# 7seg2.net
KiCad netlist of a schematic drawn in EAGLE
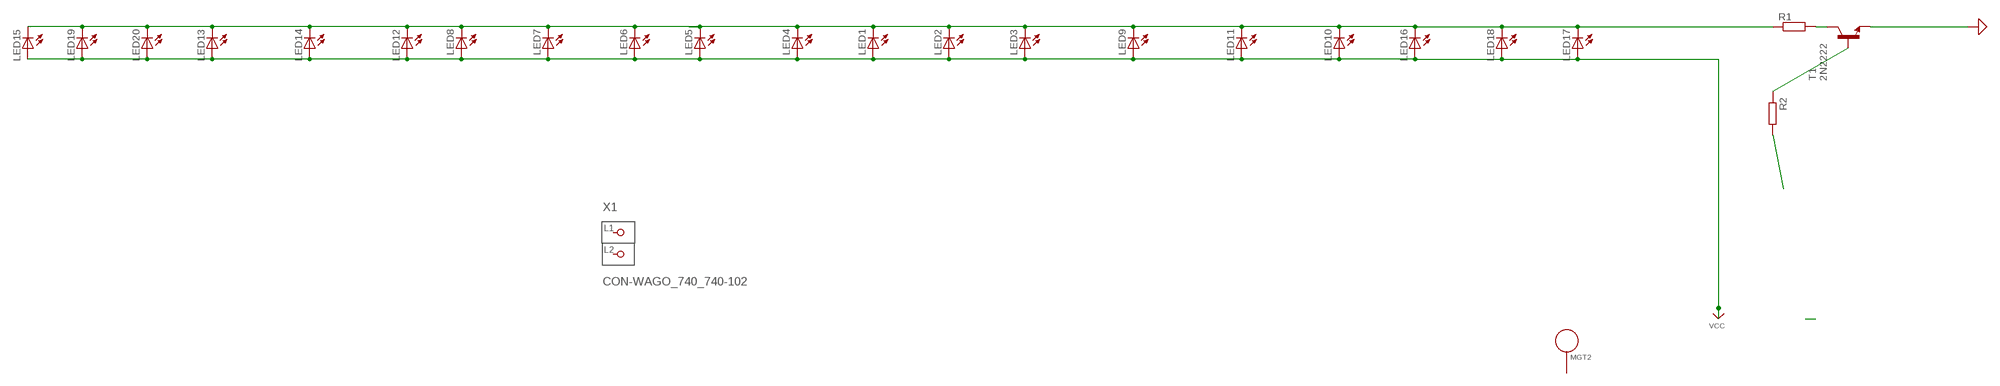
[diagram p0: schematic, sheet 1]
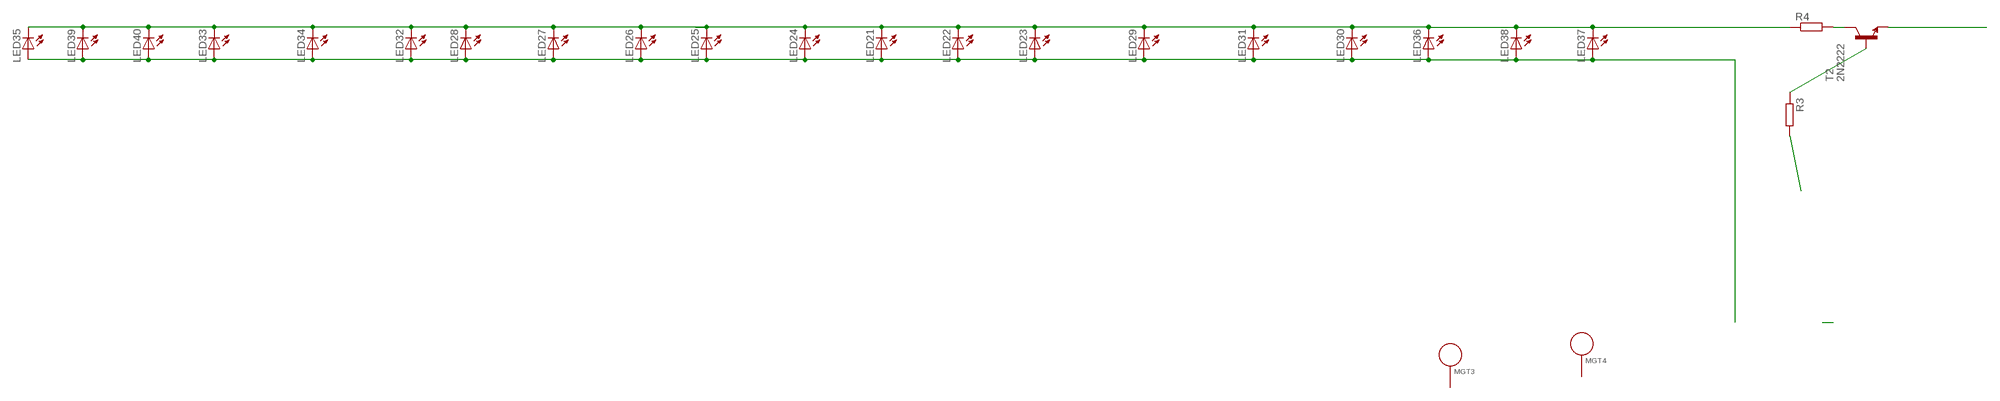
[diagram p1: schematic, sheet 2]
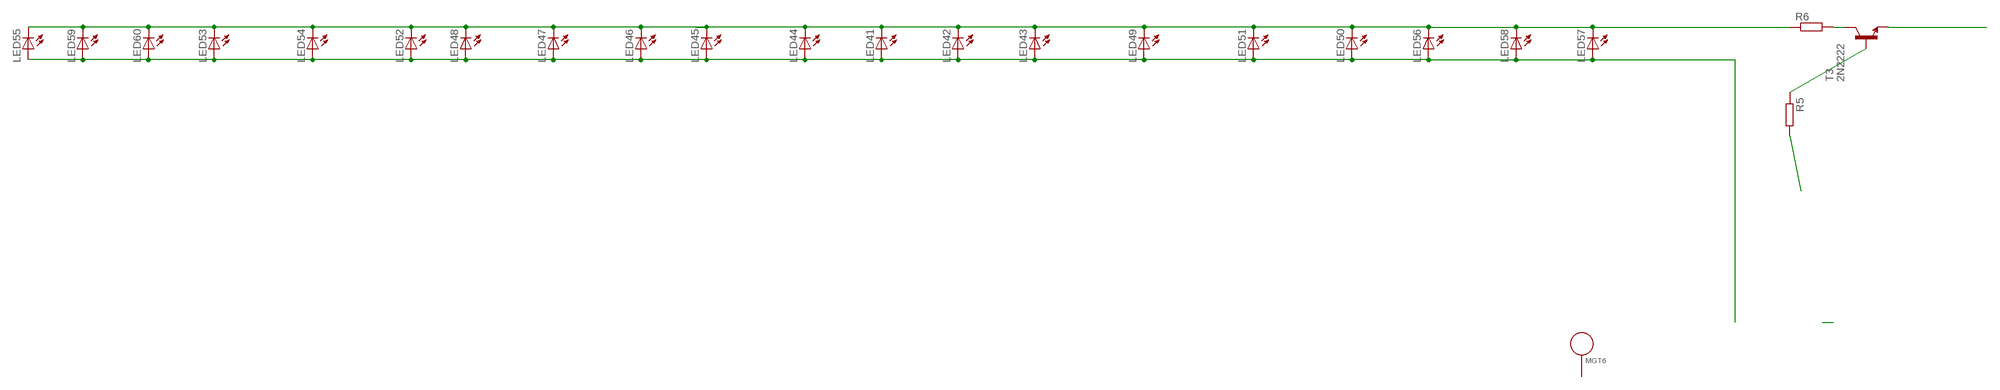
[diagram p2: schematic, sheet 3]
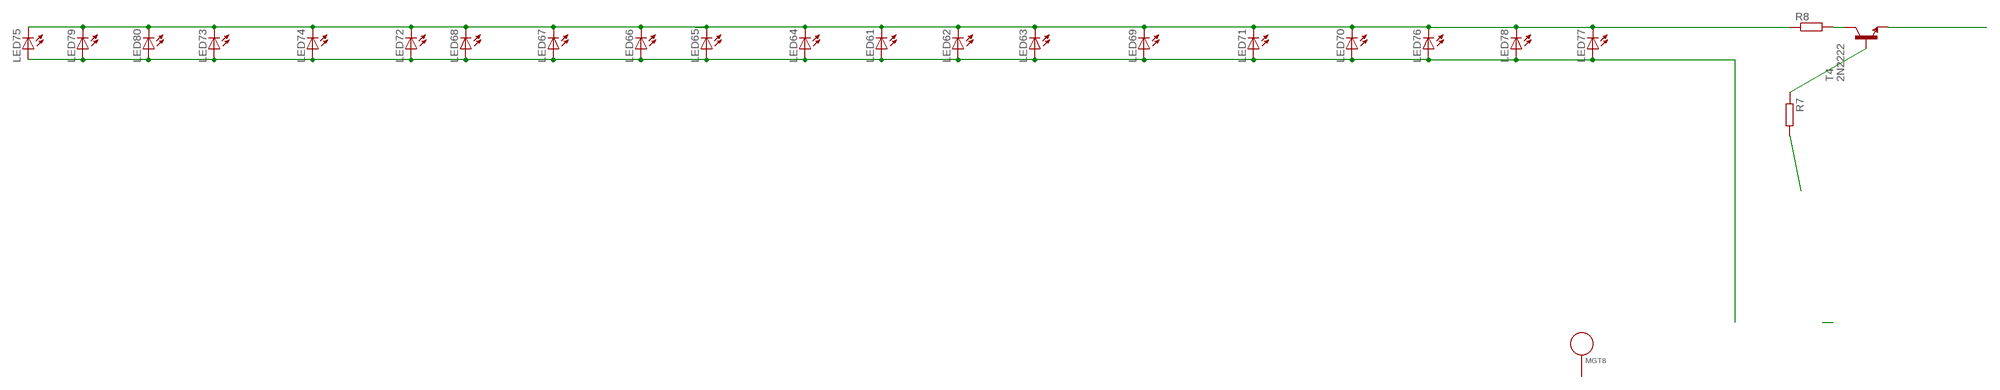
[diagram p3: schematic, sheet 4]
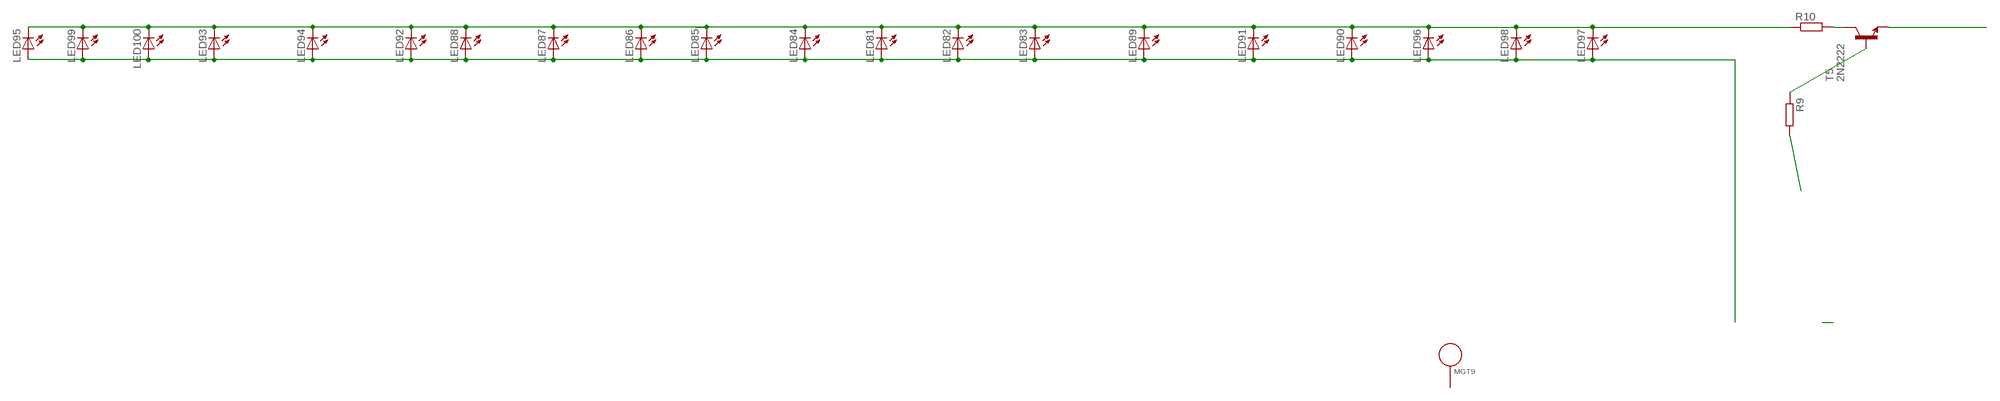
[diagram p4: schematic, sheet 5]
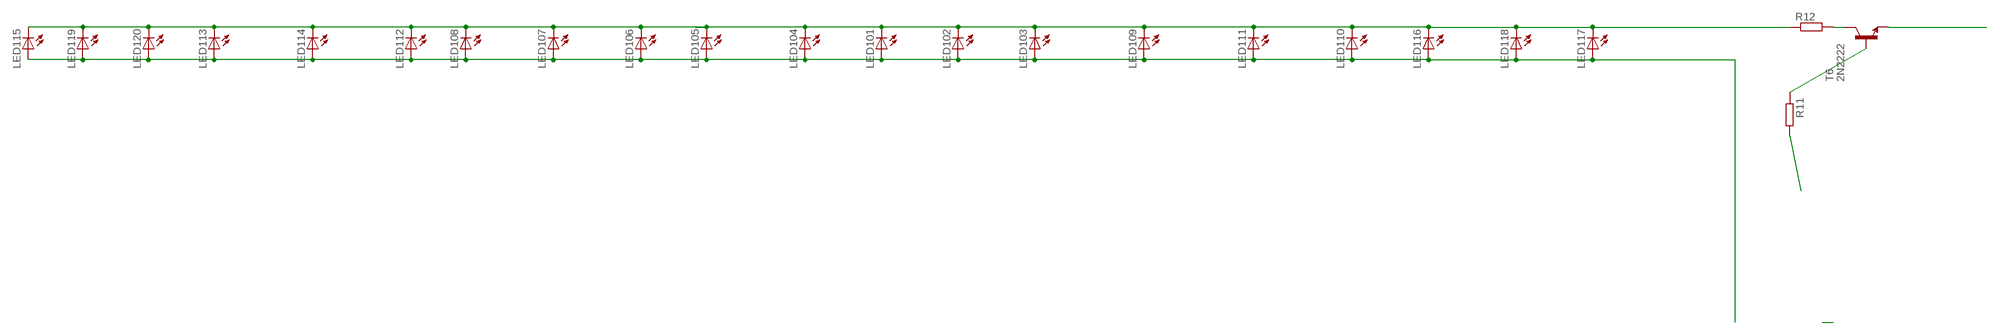
[diagram p5: schematic, sheet 6]
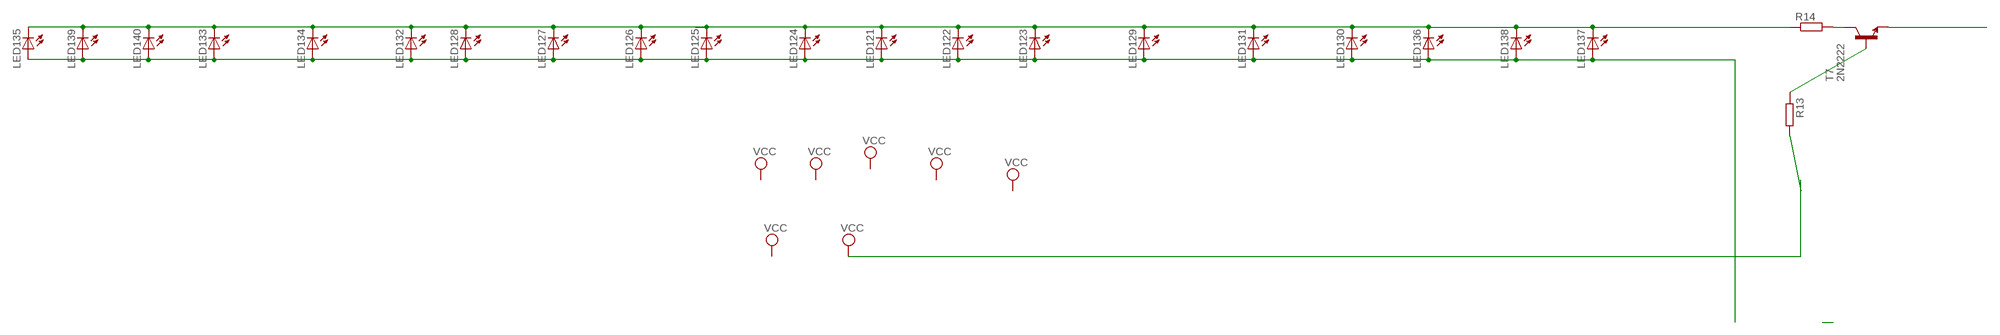
[diagram p6: schematic, sheet 7]

(export (version "E")
  (design (tool "Eeschema 10.0.6"))
  (components
    (comp (ref "LED41")
      (value "LED5MM")
      (footprint "eagle-import:LED5MM")
      (libsource (lib "eagle-import") (part "LED5MM"))
    )
    (comp (ref "LED42")
      (value "LED5MM")
      (footprint "eagle-import:LED5MM")
      (libsource (lib "eagle-import") (part "LED5MM"))
    )
    (comp (ref "LED43")
      (value "LED5MM")
      (footprint "eagle-import:LED5MM")
      (libsource (lib "eagle-import") (part "LED5MM"))
    )
    (comp (ref "LED44")
      (value "LED5MM")
      (footprint "eagle-import:LED5MM")
      (libsource (lib "eagle-import") (part "LED5MM"))
    )
    (comp (ref "LED45")
      (value "LED5MM")
      (footprint "eagle-import:LED5MM")
      (libsource (lib "eagle-import") (part "LED5MM"))
    )
    (comp (ref "LED46")
      (value "LED5MM")
      (footprint "eagle-import:LED5MM")
      (libsource (lib "eagle-import") (part "LED5MM"))
    )
    (comp (ref "LED47")
      (value "LED5MM")
      (footprint "eagle-import:LED5MM")
      (libsource (lib "eagle-import") (part "LED5MM"))
    )
    (comp (ref "LED48")
      (value "LED5MM")
      (footprint "eagle-import:LED5MM")
      (libsource (lib "eagle-import") (part "LED5MM"))
    )
    (comp (ref "LED49")
      (value "LED5MM")
      (footprint "eagle-import:LED5MM")
      (libsource (lib "eagle-import") (part "LED5MM"))
    )
    (comp (ref "LED50")
      (value "LED5MM")
      (footprint "eagle-import:LED5MM")
      (libsource (lib "eagle-import") (part "LED5MM"))
    )
    (comp (ref "LED51")
      (value "LED5MM")
      (footprint "eagle-import:LED5MM")
      (libsource (lib "eagle-import") (part "LED5MM"))
    )
    (comp (ref "LED52")
      (value "LED5MM")
      (footprint "eagle-import:LED5MM")
      (libsource (lib "eagle-import") (part "LED5MM"))
    )
    (comp (ref "LED53")
      (value "LED5MM")
      (footprint "eagle-import:LED5MM")
      (libsource (lib "eagle-import") (part "LED5MM"))
    )
    (comp (ref "LED54")
      (value "LED5MM")
      (footprint "eagle-import:LED5MM")
      (libsource (lib "eagle-import") (part "LED5MM"))
    )
    (comp (ref "LED55")
      (value "LED5MM")
      (footprint "eagle-import:LED5MM")
      (libsource (lib "eagle-import") (part "LED5MM"))
    )
    (comp (ref "LED56")
      (value "LED5MM")
      (footprint "eagle-import:LED5MM")
      (libsource (lib "eagle-import") (part "LED5MM"))
    )
    (comp (ref "LED57")
      (value "LED5MM")
      (footprint "eagle-import:LED5MM")
      (libsource (lib "eagle-import") (part "LED5MM"))
    )
    (comp (ref "LED58")
      (value "LED5MM")
      (footprint "eagle-import:LED5MM")
      (libsource (lib "eagle-import") (part "LED5MM"))
    )
    (comp (ref "LED59")
      (value "LED5MM")
      (footprint "eagle-import:LED5MM")
      (libsource (lib "eagle-import") (part "LED5MM"))
    )
    (comp (ref "LED60")
      (value "LED5MM")
      (footprint "eagle-import:LED5MM")
      (libsource (lib "eagle-import") (part "LED5MM"))
    )
    (comp (ref "MGT6")
      (value "BEAGLEBONEBLACK_MOUNTING_HOLE")
      (footprint "eagle-import:BEAGLEBONEBLACK_MOUNTING_HOLE")
      (libsource (lib "eagle-import") (part "BEAGLEBONEBLACK_MOUNTING_HOLE"))
    )
    (comp (ref "R5")
      (value "R-EU_0207/10")
      (footprint "eagle-import:0207_10")
      (libsource (lib "eagle-import") (part "R-EU_0207/10"))
    )
    (comp (ref "R6")
      (value "R-EU_0207/10")
      (footprint "eagle-import:0207_10")
      (libsource (lib "eagle-import") (part "R-EU_0207/10"))
    )
    (comp (ref "T3")
      (value "2N2222")
      (footprint "eagle-import:TO92-EBC-OVAL")
      (libsource (lib "eagle-import") (part "2N2222"))
    )
    (comp (ref "LED101")
      (value "LED5MM")
      (footprint "eagle-import:LED5MM")
      (libsource (lib "eagle-import") (part "LED5MM"))
    )
    (comp (ref "LED102")
      (value "LED5MM")
      (footprint "eagle-import:LED5MM")
      (libsource (lib "eagle-import") (part "LED5MM"))
    )
    (comp (ref "LED103")
      (value "LED5MM")
      (footprint "eagle-import:LED5MM")
      (libsource (lib "eagle-import") (part "LED5MM"))
    )
    (comp (ref "LED104")
      (value "LED5MM")
      (footprint "eagle-import:LED5MM")
      (libsource (lib "eagle-import") (part "LED5MM"))
    )
    (comp (ref "LED105")
      (value "LED5MM")
      (footprint "eagle-import:LED5MM")
      (libsource (lib "eagle-import") (part "LED5MM"))
    )
    (comp (ref "LED106")
      (value "LED5MM")
      (footprint "eagle-import:LED5MM")
      (libsource (lib "eagle-import") (part "LED5MM"))
    )
    (comp (ref "LED107")
      (value "LED5MM")
      (footprint "eagle-import:LED5MM")
      (libsource (lib "eagle-import") (part "LED5MM"))
    )
    (comp (ref "LED108")
      (value "LED5MM")
      (footprint "eagle-import:LED5MM")
      (libsource (lib "eagle-import") (part "LED5MM"))
    )
    (comp (ref "LED109")
      (value "LED5MM")
      (footprint "eagle-import:LED5MM")
      (libsource (lib "eagle-import") (part "LED5MM"))
    )
    (comp (ref "LED110")
      (value "LED5MM")
      (footprint "eagle-import:LED5MM")
      (libsource (lib "eagle-import") (part "LED5MM"))
    )
    (comp (ref "LED111")
      (value "LED5MM")
      (footprint "eagle-import:LED5MM")
      (libsource (lib "eagle-import") (part "LED5MM"))
    )
    (comp (ref "LED112")
      (value "LED5MM")
      (footprint "eagle-import:LED5MM")
      (libsource (lib "eagle-import") (part "LED5MM"))
    )
    (comp (ref "LED113")
      (value "LED5MM")
      (footprint "eagle-import:LED5MM")
      (libsource (lib "eagle-import") (part "LED5MM"))
    )
    (comp (ref "LED114")
      (value "LED5MM")
      (footprint "eagle-import:LED5MM")
      (libsource (lib "eagle-import") (part "LED5MM"))
    )
    (comp (ref "LED115")
      (value "LED5MM")
      (footprint "eagle-import:LED5MM")
      (libsource (lib "eagle-import") (part "LED5MM"))
    )
    (comp (ref "LED116")
      (value "LED5MM")
      (footprint "eagle-import:LED5MM")
      (libsource (lib "eagle-import") (part "LED5MM"))
    )
    (comp (ref "LED117")
      (value "LED5MM")
      (footprint "eagle-import:LED5MM")
      (libsource (lib "eagle-import") (part "LED5MM"))
    )
    (comp (ref "LED118")
      (value "LED5MM")
      (footprint "eagle-import:LED5MM")
      (libsource (lib "eagle-import") (part "LED5MM"))
    )
    (comp (ref "LED119")
      (value "LED5MM")
      (footprint "eagle-import:LED5MM")
      (libsource (lib "eagle-import") (part "LED5MM"))
    )
    (comp (ref "LED120")
      (value "LED5MM")
      (footprint "eagle-import:LED5MM")
      (libsource (lib "eagle-import") (part "LED5MM"))
    )
    (comp (ref "R11")
      (value "R-EU_0207/10")
      (footprint "eagle-import:0207_10")
      (libsource (lib "eagle-import") (part "R-EU_0207/10"))
    )
    (comp (ref "R12")
      (value "R-EU_0207/10")
      (footprint "eagle-import:0207_10")
      (libsource (lib "eagle-import") (part "R-EU_0207/10"))
    )
    (comp (ref "T6")
      (value "2N2222")
      (footprint "eagle-import:TO92-EBC-OVAL")
      (libsource (lib "eagle-import") (part "2N2222"))
    )
    (comp (ref "LED81")
      (value "LED5MM")
      (footprint "eagle-import:LED5MM")
      (libsource (lib "eagle-import") (part "LED5MM"))
    )
    (comp (ref "LED82")
      (value "LED5MM")
      (footprint "eagle-import:LED5MM")
      (libsource (lib "eagle-import") (part "LED5MM"))
    )
    (comp (ref "LED83")
      (value "LED5MM")
      (footprint "eagle-import:LED5MM")
      (libsource (lib "eagle-import") (part "LED5MM"))
    )
    (comp (ref "LED84")
      (value "LED5MM")
      (footprint "eagle-import:LED5MM")
      (libsource (lib "eagle-import") (part "LED5MM"))
    )
    (comp (ref "LED85")
      (value "LED5MM")
      (footprint "eagle-import:LED5MM")
      (libsource (lib "eagle-import") (part "LED5MM"))
    )
    (comp (ref "LED86")
      (value "LED5MM")
      (footprint "eagle-import:LED5MM")
      (libsource (lib "eagle-import") (part "LED5MM"))
    )
    (comp (ref "LED87")
      (value "LED5MM")
      (footprint "eagle-import:LED5MM")
      (libsource (lib "eagle-import") (part "LED5MM"))
    )
    (comp (ref "LED88")
      (value "LED5MM")
      (footprint "eagle-import:LED5MM")
      (libsource (lib "eagle-import") (part "LED5MM"))
    )
    (comp (ref "LED89")
      (value "LED5MM")
      (footprint "eagle-import:LED5MM")
      (libsource (lib "eagle-import") (part "LED5MM"))
    )
    (comp (ref "LED90")
      (value "LED5MM")
      (footprint "eagle-import:LED5MM")
      (libsource (lib "eagle-import") (part "LED5MM"))
    )
    (comp (ref "LED91")
      (value "LED5MM")
      (footprint "eagle-import:LED5MM")
      (libsource (lib "eagle-import") (part "LED5MM"))
    )
    (comp (ref "LED92")
      (value "LED5MM")
      (footprint "eagle-import:LED5MM")
      (libsource (lib "eagle-import") (part "LED5MM"))
    )
    (comp (ref "LED93")
      (value "LED5MM")
      (footprint "eagle-import:LED5MM")
      (libsource (lib "eagle-import") (part "LED5MM"))
    )
    (comp (ref "LED94")
      (value "LED5MM")
      (footprint "eagle-import:LED5MM")
      (libsource (lib "eagle-import") (part "LED5MM"))
    )
    (comp (ref "LED95")
      (value "LED5MM")
      (footprint "eagle-import:LED5MM")
      (libsource (lib "eagle-import") (part "LED5MM"))
    )
    (comp (ref "LED96")
      (value "LED5MM")
      (footprint "eagle-import:LED5MM")
      (libsource (lib "eagle-import") (part "LED5MM"))
    )
    (comp (ref "LED97")
      (value "LED5MM")
      (footprint "eagle-import:LED5MM")
      (libsource (lib "eagle-import") (part "LED5MM"))
    )
    (comp (ref "LED98")
      (value "LED5MM")
      (footprint "eagle-import:LED5MM")
      (libsource (lib "eagle-import") (part "LED5MM"))
    )
    (comp (ref "LED99")
      (value "LED5MM")
      (footprint "eagle-import:LED5MM")
      (libsource (lib "eagle-import") (part "LED5MM"))
    )
    (comp (ref "LED100")
      (value "LED5MM")
      (footprint "eagle-import:LED5MM")
      (libsource (lib "eagle-import") (part "LED5MM"))
    )
    (comp (ref "MGT9")
      (value "BEAGLEBONEBLACK_MOUNTING_HOLE")
      (footprint "eagle-import:BEAGLEBONEBLACK_MOUNTING_HOLE")
      (libsource (lib "eagle-import") (part "BEAGLEBONEBLACK_MOUNTING_HOLE"))
    )
    (comp (ref "R9")
      (value "R-EU_0207/10")
      (footprint "eagle-import:0207_10")
      (libsource (lib "eagle-import") (part "R-EU_0207/10"))
    )
    (comp (ref "R10")
      (value "R-EU_0207/10")
      (footprint "eagle-import:0207_10")
      (libsource (lib "eagle-import") (part "R-EU_0207/10"))
    )
    (comp (ref "T5")
      (value "2N2222")
      (footprint "eagle-import:TO92-EBC-OVAL")
      (libsource (lib "eagle-import") (part "2N2222"))
    )
    (comp (ref "LED21")
      (value "LED5MM")
      (footprint "eagle-import:LED5MM")
      (libsource (lib "eagle-import") (part "LED5MM"))
    )
    (comp (ref "LED22")
      (value "LED5MM")
      (footprint "eagle-import:LED5MM")
      (libsource (lib "eagle-import") (part "LED5MM"))
    )
    (comp (ref "LED23")
      (value "LED5MM")
      (footprint "eagle-import:LED5MM")
      (libsource (lib "eagle-import") (part "LED5MM"))
    )
    (comp (ref "LED24")
      (value "LED5MM")
      (footprint "eagle-import:LED5MM")
      (libsource (lib "eagle-import") (part "LED5MM"))
    )
    (comp (ref "LED25")
      (value "LED5MM")
      (footprint "eagle-import:LED5MM")
      (libsource (lib "eagle-import") (part "LED5MM"))
    )
    (comp (ref "LED26")
      (value "LED5MM")
      (footprint "eagle-import:LED5MM")
      (libsource (lib "eagle-import") (part "LED5MM"))
    )
    (comp (ref "LED27")
      (value "LED5MM")
      (footprint "eagle-import:LED5MM")
      (libsource (lib "eagle-import") (part "LED5MM"))
    )
    (comp (ref "LED28")
      (value "LED5MM")
      (footprint "eagle-import:LED5MM")
      (libsource (lib "eagle-import") (part "LED5MM"))
    )
    (comp (ref "LED29")
      (value "LED5MM")
      (footprint "eagle-import:LED5MM")
      (libsource (lib "eagle-import") (part "LED5MM"))
    )
    (comp (ref "LED30")
      (value "LED5MM")
      (footprint "eagle-import:LED5MM")
      (libsource (lib "eagle-import") (part "LED5MM"))
    )
    (comp (ref "LED31")
      (value "LED5MM")
      (footprint "eagle-import:LED5MM")
      (libsource (lib "eagle-import") (part "LED5MM"))
    )
    (comp (ref "LED32")
      (value "LED5MM")
      (footprint "eagle-import:LED5MM")
      (libsource (lib "eagle-import") (part "LED5MM"))
    )
    (comp (ref "LED33")
      (value "LED5MM")
      (footprint "eagle-import:LED5MM")
      (libsource (lib "eagle-import") (part "LED5MM"))
    )
    (comp (ref "LED34")
      (value "LED5MM")
      (footprint "eagle-import:LED5MM")
      (libsource (lib "eagle-import") (part "LED5MM"))
    )
    (comp (ref "LED35")
      (value "LED5MM")
      (footprint "eagle-import:LED5MM")
      (libsource (lib "eagle-import") (part "LED5MM"))
    )
    (comp (ref "LED36")
      (value "LED5MM")
      (footprint "eagle-import:LED5MM")
      (libsource (lib "eagle-import") (part "LED5MM"))
    )
    (comp (ref "LED37")
      (value "LED5MM")
      (footprint "eagle-import:LED5MM")
      (libsource (lib "eagle-import") (part "LED5MM"))
    )
    (comp (ref "LED38")
      (value "LED5MM")
      (footprint "eagle-import:LED5MM")
      (libsource (lib "eagle-import") (part "LED5MM"))
    )
    (comp (ref "LED39")
      (value "LED5MM")
      (footprint "eagle-import:LED5MM")
      (libsource (lib "eagle-import") (part "LED5MM"))
    )
    (comp (ref "LED40")
      (value "LED5MM")
      (footprint "eagle-import:LED5MM")
      (libsource (lib "eagle-import") (part "LED5MM"))
    )
    (comp (ref "MGT3")
      (value "BEAGLEBONEBLACK_MOUNTING_HOLE")
      (footprint "eagle-import:BEAGLEBONEBLACK_MOUNTING_HOLE")
      (libsource (lib "eagle-import") (part "BEAGLEBONEBLACK_MOUNTING_HOLE"))
    )
    (comp (ref "MGT4")
      (value "BEAGLEBONEBLACK_MOUNTING_HOLE")
      (footprint "eagle-import:BEAGLEBONEBLACK_MOUNTING_HOLE")
      (libsource (lib "eagle-import") (part "BEAGLEBONEBLACK_MOUNTING_HOLE"))
    )
    (comp (ref "R3")
      (value "R-EU_0207/10")
      (footprint "eagle-import:0207_10")
      (libsource (lib "eagle-import") (part "R-EU_0207/10"))
    )
    (comp (ref "R4")
      (value "R-EU_0207/10")
      (footprint "eagle-import:0207_10")
      (libsource (lib "eagle-import") (part "R-EU_0207/10"))
    )
    (comp (ref "T2")
      (value "2N2222")
      (footprint "eagle-import:TO92-EBC-OVAL")
      (libsource (lib "eagle-import") (part "2N2222"))
    )
    (comp (ref "LED1")
      (value "LED5MM")
      (footprint "eagle-import:LED5MM")
      (libsource (lib "eagle-import") (part "LED5MM"))
    )
    (comp (ref "LED2")
      (value "LED5MM")
      (footprint "eagle-import:LED5MM")
      (libsource (lib "eagle-import") (part "LED5MM"))
    )
    (comp (ref "LED3")
      (value "LED5MM")
      (footprint "eagle-import:LED5MM")
      (libsource (lib "eagle-import") (part "LED5MM"))
    )
    (comp (ref "LED4")
      (value "LED5MM")
      (footprint "eagle-import:LED5MM")
      (libsource (lib "eagle-import") (part "LED5MM"))
    )
    (comp (ref "LED5")
      (value "LED5MM")
      (footprint "eagle-import:LED5MM")
      (libsource (lib "eagle-import") (part "LED5MM"))
    )
    (comp (ref "LED6")
      (value "LED5MM")
      (footprint "eagle-import:LED5MM")
      (libsource (lib "eagle-import") (part "LED5MM"))
    )
    (comp (ref "LED7")
      (value "LED5MM")
      (footprint "eagle-import:LED5MM")
      (libsource (lib "eagle-import") (part "LED5MM"))
    )
    (comp (ref "LED8")
      (value "LED5MM")
      (footprint "eagle-import:LED5MM")
      (libsource (lib "eagle-import") (part "LED5MM"))
    )
    (comp (ref "LED9")
      (value "LED5MM")
      (footprint "eagle-import:LED5MM")
      (libsource (lib "eagle-import") (part "LED5MM"))
    )
    (comp (ref "LED10")
      (value "LED5MM")
      (footprint "eagle-import:LED5MM")
      (libsource (lib "eagle-import") (part "LED5MM"))
    )
    (comp (ref "LED11")
      (value "LED5MM")
      (footprint "eagle-import:LED5MM")
      (libsource (lib "eagle-import") (part "LED5MM"))
    )
    (comp (ref "LED12")
      (value "LED5MM")
      (footprint "eagle-import:LED5MM")
      (libsource (lib "eagle-import") (part "LED5MM"))
    )
    (comp (ref "LED13")
      (value "LED5MM")
      (footprint "eagle-import:LED5MM")
      (libsource (lib "eagle-import") (part "LED5MM"))
    )
    (comp (ref "LED14")
      (value "LED5MM")
      (footprint "eagle-import:LED5MM")
      (libsource (lib "eagle-import") (part "LED5MM"))
    )
    (comp (ref "LED15")
      (value "LED5MM")
      (footprint "eagle-import:LED5MM")
      (libsource (lib "eagle-import") (part "LED5MM"))
    )
    (comp (ref "LED16")
      (value "LED5MM")
      (footprint "eagle-import:LED5MM")
      (libsource (lib "eagle-import") (part "LED5MM"))
    )
    (comp (ref "LED17")
      (value "LED5MM")
      (footprint "eagle-import:LED5MM")
      (libsource (lib "eagle-import") (part "LED5MM"))
    )
    (comp (ref "LED18")
      (value "LED5MM")
      (footprint "eagle-import:LED5MM")
      (libsource (lib "eagle-import") (part "LED5MM"))
    )
    (comp (ref "LED19")
      (value "LED5MM")
      (footprint "eagle-import:LED5MM")
      (libsource (lib "eagle-import") (part "LED5MM"))
    )
    (comp (ref "LED20")
      (value "LED5MM")
      (footprint "eagle-import:LED5MM")
      (libsource (lib "eagle-import") (part "LED5MM"))
    )
    (comp (ref "MGT2")
      (value "BEAGLEBONEBLACK_MOUNTING_HOLE")
      (footprint "eagle-import:BEAGLEBONEBLACK_MOUNTING_HOLE")
      (libsource (lib "eagle-import") (part "BEAGLEBONEBLACK_MOUNTING_HOLE"))
    )
    (comp (ref "R1")
      (value "R-EU_0207/10")
      (footprint "eagle-import:0207_10")
      (libsource (lib "eagle-import") (part "R-EU_0207/10"))
    )
    (comp (ref "R2")
      (value "R-EU_0207/10")
      (footprint "eagle-import:0207_10")
      (libsource (lib "eagle-import") (part "R-EU_0207/10"))
    )
    (comp (ref "T1")
      (value "2N2222")
      (footprint "eagle-import:TO92-EBC-OVAL")
      (libsource (lib "eagle-import") (part "2N2222"))
    )
    (comp (ref "X1")
      (value "CON-WAGO_740_740-102")
      (footprint "eagle-import:CON-WAGO_740_P-740-102")
      (libsource (lib "eagle-import") (part "CON-WAGO_740_740-102"))
    )
    (comp (ref "LED121")
      (value "LED5MM")
      (footprint "eagle-import:LED5MM")
      (libsource (lib "eagle-import") (part "LED5MM"))
    )
    (comp (ref "LED122")
      (value "LED5MM")
      (footprint "eagle-import:LED5MM")
      (libsource (lib "eagle-import") (part "LED5MM"))
    )
    (comp (ref "LED123")
      (value "LED5MM")
      (footprint "eagle-import:LED5MM")
      (libsource (lib "eagle-import") (part "LED5MM"))
    )
    (comp (ref "LED124")
      (value "LED5MM")
      (footprint "eagle-import:LED5MM")
      (libsource (lib "eagle-import") (part "LED5MM"))
    )
    (comp (ref "LED125")
      (value "LED5MM")
      (footprint "eagle-import:LED5MM")
      (libsource (lib "eagle-import") (part "LED5MM"))
    )
    (comp (ref "LED126")
      (value "LED5MM")
      (footprint "eagle-import:LED5MM")
      (libsource (lib "eagle-import") (part "LED5MM"))
    )
    (comp (ref "LED127")
      (value "LED5MM")
      (footprint "eagle-import:LED5MM")
      (libsource (lib "eagle-import") (part "LED5MM"))
    )
    (comp (ref "LED128")
      (value "LED5MM")
      (footprint "eagle-import:LED5MM")
      (libsource (lib "eagle-import") (part "LED5MM"))
    )
    (comp (ref "LED129")
      (value "LED5MM")
      (footprint "eagle-import:LED5MM")
      (libsource (lib "eagle-import") (part "LED5MM"))
    )
    (comp (ref "LED130")
      (value "LED5MM")
      (footprint "eagle-import:LED5MM")
      (libsource (lib "eagle-import") (part "LED5MM"))
    )
    (comp (ref "LED131")
      (value "LED5MM")
      (footprint "eagle-import:LED5MM")
      (libsource (lib "eagle-import") (part "LED5MM"))
    )
    (comp (ref "LED132")
      (value "LED5MM")
      (footprint "eagle-import:LED5MM")
      (libsource (lib "eagle-import") (part "LED5MM"))
    )
    (comp (ref "LED133")
      (value "LED5MM")
      (footprint "eagle-import:LED5MM")
      (libsource (lib "eagle-import") (part "LED5MM"))
    )
    (comp (ref "LED134")
      (value "LED5MM")
      (footprint "eagle-import:LED5MM")
      (libsource (lib "eagle-import") (part "LED5MM"))
    )
    (comp (ref "LED135")
      (value "LED5MM")
      (footprint "eagle-import:LED5MM")
      (libsource (lib "eagle-import") (part "LED5MM"))
    )
    (comp (ref "LED136")
      (value "LED5MM")
      (footprint "eagle-import:LED5MM")
      (libsource (lib "eagle-import") (part "LED5MM"))
    )
    (comp (ref "LED137")
      (value "LED5MM")
      (footprint "eagle-import:LED5MM")
      (libsource (lib "eagle-import") (part "LED5MM"))
    )
    (comp (ref "LED138")
      (value "LED5MM")
      (footprint "eagle-import:LED5MM")
      (libsource (lib "eagle-import") (part "LED5MM"))
    )
    (comp (ref "LED139")
      (value "LED5MM")
      (footprint "eagle-import:LED5MM")
      (libsource (lib "eagle-import") (part "LED5MM"))
    )
    (comp (ref "LED140")
      (value "LED5MM")
      (footprint "eagle-import:LED5MM")
      (libsource (lib "eagle-import") (part "LED5MM"))
    )
    (comp (ref "R13")
      (value "R-EU_0207/10")
      (footprint "eagle-import:0207_10")
      (libsource (lib "eagle-import") (part "R-EU_0207/10"))
    )
    (comp (ref "R14")
      (value "R-EU_0207/10")
      (footprint "eagle-import:0207_10")
      (libsource (lib "eagle-import") (part "R-EU_0207/10"))
    )
    (comp (ref "T7")
      (value "2N2222")
      (footprint "eagle-import:TO92-EBC-OVAL")
      (libsource (lib "eagle-import") (part "2N2222"))
    )
    (comp (ref "LED61")
      (value "LED5MM")
      (footprint "eagle-import:LED5MM")
      (libsource (lib "eagle-import") (part "LED5MM"))
    )
    (comp (ref "LED62")
      (value "LED5MM")
      (footprint "eagle-import:LED5MM")
      (libsource (lib "eagle-import") (part "LED5MM"))
    )
    (comp (ref "LED63")
      (value "LED5MM")
      (footprint "eagle-import:LED5MM")
      (libsource (lib "eagle-import") (part "LED5MM"))
    )
    (comp (ref "LED64")
      (value "LED5MM")
      (footprint "eagle-import:LED5MM")
      (libsource (lib "eagle-import") (part "LED5MM"))
    )
    (comp (ref "LED65")
      (value "LED5MM")
      (footprint "eagle-import:LED5MM")
      (libsource (lib "eagle-import") (part "LED5MM"))
    )
    (comp (ref "LED66")
      (value "LED5MM")
      (footprint "eagle-import:LED5MM")
      (libsource (lib "eagle-import") (part "LED5MM"))
    )
    (comp (ref "LED67")
      (value "LED5MM")
      (footprint "eagle-import:LED5MM")
      (libsource (lib "eagle-import") (part "LED5MM"))
    )
    (comp (ref "LED68")
      (value "LED5MM")
      (footprint "eagle-import:LED5MM")
      (libsource (lib "eagle-import") (part "LED5MM"))
    )
    (comp (ref "LED69")
      (value "LED5MM")
      (footprint "eagle-import:LED5MM")
      (libsource (lib "eagle-import") (part "LED5MM"))
    )
    (comp (ref "LED70")
      (value "LED5MM")
      (footprint "eagle-import:LED5MM")
      (libsource (lib "eagle-import") (part "LED5MM"))
    )
    (comp (ref "LED71")
      (value "LED5MM")
      (footprint "eagle-import:LED5MM")
      (libsource (lib "eagle-import") (part "LED5MM"))
    )
    (comp (ref "LED72")
      (value "LED5MM")
      (footprint "eagle-import:LED5MM")
      (libsource (lib "eagle-import") (part "LED5MM"))
    )
    (comp (ref "LED73")
      (value "LED5MM")
      (footprint "eagle-import:LED5MM")
      (libsource (lib "eagle-import") (part "LED5MM"))
    )
    (comp (ref "LED74")
      (value "LED5MM")
      (footprint "eagle-import:LED5MM")
      (libsource (lib "eagle-import") (part "LED5MM"))
    )
    (comp (ref "LED75")
      (value "LED5MM")
      (footprint "eagle-import:LED5MM")
      (libsource (lib "eagle-import") (part "LED5MM"))
    )
    (comp (ref "LED76")
      (value "LED5MM")
      (footprint "eagle-import:LED5MM")
      (libsource (lib "eagle-import") (part "LED5MM"))
    )
    (comp (ref "LED77")
      (value "LED5MM")
      (footprint "eagle-import:LED5MM")
      (libsource (lib "eagle-import") (part "LED5MM"))
    )
    (comp (ref "LED78")
      (value "LED5MM")
      (footprint "eagle-import:LED5MM")
      (libsource (lib "eagle-import") (part "LED5MM"))
    )
    (comp (ref "LED79")
      (value "LED5MM")
      (footprint "eagle-import:LED5MM")
      (libsource (lib "eagle-import") (part "LED5MM"))
    )
    (comp (ref "LED80")
      (value "LED5MM")
      (footprint "eagle-import:LED5MM")
      (libsource (lib "eagle-import") (part "LED5MM"))
    )
    (comp (ref "MGT8")
      (value "BEAGLEBONEBLACK_MOUNTING_HOLE")
      (footprint "eagle-import:BEAGLEBONEBLACK_MOUNTING_HOLE")
      (libsource (lib "eagle-import") (part "BEAGLEBONEBLACK_MOUNTING_HOLE"))
    )
    (comp (ref "R7")
      (value "R-EU_0207/10")
      (footprint "eagle-import:0207_10")
      (libsource (lib "eagle-import") (part "R-EU_0207/10"))
    )
    (comp (ref "R8")
      (value "R-EU_0207/10")
      (footprint "eagle-import:0207_10")
      (libsource (lib "eagle-import") (part "R-EU_0207/10"))
    )
    (comp (ref "T4")
      (value "2N2222")
      (footprint "eagle-import:TO92-EBC-OVAL")
      (libsource (lib "eagle-import") (part "2N2222"))
    )
  )
  (nets
    (net (code "1") (name "Net-(LED1-C)") (class "Default")
      (node (ref "LED1") (pin "K") (pinfunction "C_K") (pintype "passive"))
      (node (ref "LED10") (pin "K") (pinfunction "C_K") (pintype "passive"))
      (node (ref "LED11") (pin "K") (pinfunction "C_K") (pintype "passive"))
      (node (ref "LED12") (pin "K") (pinfunction "C_K") (pintype "passive"))
      (node (ref "LED13") (pin "K") (pinfunction "C_K") (pintype "passive"))
      (node (ref "LED14") (pin "K") (pinfunction "C_K") (pintype "passive"))
      (node (ref "LED15") (pin "K") (pinfunction "C_K") (pintype "passive"))
      (node (ref "LED16") (pin "K") (pinfunction "C_K") (pintype "passive"))
      (node (ref "LED17") (pin "K") (pinfunction "C_K") (pintype "passive"))
      (node (ref "LED18") (pin "K") (pinfunction "C_K") (pintype "passive"))
      (node (ref "LED19") (pin "K") (pinfunction "C_K") (pintype "passive"))
      (node (ref "LED2") (pin "K") (pinfunction "C_K") (pintype "passive"))
      (node (ref "LED20") (pin "K") (pinfunction "C_K") (pintype "passive"))
      (node (ref "LED3") (pin "K") (pinfunction "C_K") (pintype "passive"))
      (node (ref "LED4") (pin "K") (pinfunction "C_K") (pintype "passive"))
      (node (ref "LED5") (pin "K") (pinfunction "C_K") (pintype "passive"))
      (node (ref "LED6") (pin "K") (pinfunction "C_K") (pintype "passive"))
      (node (ref "LED7") (pin "K") (pinfunction "C_K") (pintype "passive"))
      (node (ref "LED8") (pin "K") (pinfunction "C_K") (pintype "passive"))
      (node (ref "LED9") (pin "K") (pinfunction "C_K") (pintype "passive"))
      (node (ref "R1") (pin "1") (pinfunction "1_1") (pintype "passive"))
    )
    (net (code "2") (name "Net-(LED21-C)") (class "Default")
      (node (ref "LED21") (pin "K") (pinfunction "C_K") (pintype "passive"))
      (node (ref "LED22") (pin "K") (pinfunction "C_K") (pintype "passive"))
      (node (ref "LED23") (pin "K") (pinfunction "C_K") (pintype "passive"))
      (node (ref "LED24") (pin "K") (pinfunction "C_K") (pintype "passive"))
      (node (ref "LED25") (pin "K") (pinfunction "C_K") (pintype "passive"))
      (node (ref "LED26") (pin "K") (pinfunction "C_K") (pintype "passive"))
      (node (ref "LED27") (pin "K") (pinfunction "C_K") (pintype "passive"))
      (node (ref "LED28") (pin "K") (pinfunction "C_K") (pintype "passive"))
      (node (ref "LED29") (pin "K") (pinfunction "C_K") (pintype "passive"))
      (node (ref "LED30") (pin "K") (pinfunction "C_K") (pintype "passive"))
      (node (ref "LED31") (pin "K") (pinfunction "C_K") (pintype "passive"))
      (node (ref "LED32") (pin "K") (pinfunction "C_K") (pintype "passive"))
      (node (ref "LED33") (pin "K") (pinfunction "C_K") (pintype "passive"))
      (node (ref "LED34") (pin "K") (pinfunction "C_K") (pintype "passive"))
      (node (ref "LED35") (pin "K") (pinfunction "C_K") (pintype "passive"))
      (node (ref "LED36") (pin "K") (pinfunction "C_K") (pintype "passive"))
      (node (ref "LED37") (pin "K") (pinfunction "C_K") (pintype "passive"))
      (node (ref "LED38") (pin "K") (pinfunction "C_K") (pintype "passive"))
      (node (ref "LED39") (pin "K") (pinfunction "C_K") (pintype "passive"))
      (node (ref "LED40") (pin "K") (pinfunction "C_K") (pintype "passive"))
      (node (ref "R4") (pin "1") (pinfunction "1_1") (pintype "passive"))
    )
    (net (code "3") (name "Net-(LED21-PadA)") (class "Default")
      (node (ref "LED21") (pin "A") (pinfunction "A_A") (pintype "passive"))
      (node (ref "LED22") (pin "A") (pinfunction "A_A") (pintype "passive"))
      (node (ref "LED23") (pin "A") (pinfunction "A_A") (pintype "passive"))
      (node (ref "LED24") (pin "A") (pinfunction "A_A") (pintype "passive"))
      (node (ref "LED25") (pin "A") (pinfunction "A_A") (pintype "passive"))
      (node (ref "LED26") (pin "A") (pinfunction "A_A") (pintype "passive"))
      (node (ref "LED27") (pin "A") (pinfunction "A_A") (pintype "passive"))
      (node (ref "LED28") (pin "A") (pinfunction "A_A") (pintype "passive"))
      (node (ref "LED29") (pin "A") (pinfunction "A_A") (pintype "passive"))
      (node (ref "LED30") (pin "A") (pinfunction "A_A") (pintype "passive"))
      (node (ref "LED31") (pin "A") (pinfunction "A_A") (pintype "passive"))
      (node (ref "LED32") (pin "A") (pinfunction "A_A") (pintype "passive"))
      (node (ref "LED33") (pin "A") (pinfunction "A_A") (pintype "passive"))
      (node (ref "LED34") (pin "A") (pinfunction "A_A") (pintype "passive"))
      (node (ref "LED35") (pin "A") (pinfunction "A_A") (pintype "passive"))
      (node (ref "LED36") (pin "A") (pinfunction "A_A") (pintype "passive"))
      (node (ref "LED37") (pin "A") (pinfunction "A_A") (pintype "passive"))
      (node (ref "LED38") (pin "A") (pinfunction "A_A") (pintype "passive"))
      (node (ref "LED39") (pin "A") (pinfunction "A_A") (pintype "passive"))
      (node (ref "LED40") (pin "A") (pinfunction "A_A") (pintype "passive"))
    )
    (net (code "4") (name "Net-(LED41-C)") (class "Default")
      (node (ref "LED41") (pin "K") (pinfunction "C_K") (pintype "passive"))
      (node (ref "LED42") (pin "K") (pinfunction "C_K") (pintype "passive"))
      (node (ref "LED43") (pin "K") (pinfunction "C_K") (pintype "passive"))
      (node (ref "LED44") (pin "K") (pinfunction "C_K") (pintype "passive"))
      (node (ref "LED45") (pin "K") (pinfunction "C_K") (pintype "passive"))
      (node (ref "LED46") (pin "K") (pinfunction "C_K") (pintype "passive"))
      (node (ref "LED47") (pin "K") (pinfunction "C_K") (pintype "passive"))
      (node (ref "LED48") (pin "K") (pinfunction "C_K") (pintype "passive"))
      (node (ref "LED49") (pin "K") (pinfunction "C_K") (pintype "passive"))
      (node (ref "LED50") (pin "K") (pinfunction "C_K") (pintype "passive"))
      (node (ref "LED51") (pin "K") (pinfunction "C_K") (pintype "passive"))
      (node (ref "LED52") (pin "K") (pinfunction "C_K") (pintype "passive"))
      (node (ref "LED53") (pin "K") (pinfunction "C_K") (pintype "passive"))
      (node (ref "LED54") (pin "K") (pinfunction "C_K") (pintype "passive"))
      (node (ref "LED55") (pin "K") (pinfunction "C_K") (pintype "passive"))
      (node (ref "LED56") (pin "K") (pinfunction "C_K") (pintype "passive"))
      (node (ref "LED57") (pin "K") (pinfunction "C_K") (pintype "passive"))
      (node (ref "LED58") (pin "K") (pinfunction "C_K") (pintype "passive"))
      (node (ref "LED59") (pin "K") (pinfunction "C_K") (pintype "passive"))
      (node (ref "LED60") (pin "K") (pinfunction "C_K") (pintype "passive"))
      (node (ref "R6") (pin "1") (pinfunction "1_1") (pintype "passive"))
    )
    (net (code "5") (name "Net-(LED41-PadA)") (class "Default")
      (node (ref "LED41") (pin "A") (pinfunction "A_A") (pintype "passive"))
      (node (ref "LED42") (pin "A") (pinfunction "A_A") (pintype "passive"))
      (node (ref "LED43") (pin "A") (pinfunction "A_A") (pintype "passive"))
      (node (ref "LED44") (pin "A") (pinfunction "A_A") (pintype "passive"))
      (node (ref "LED45") (pin "A") (pinfunction "A_A") (pintype "passive"))
      (node (ref "LED46") (pin "A") (pinfunction "A_A") (pintype "passive"))
      (node (ref "LED47") (pin "A") (pinfunction "A_A") (pintype "passive"))
      (node (ref "LED48") (pin "A") (pinfunction "A_A") (pintype "passive"))
      (node (ref "LED49") (pin "A") (pinfunction "A_A") (pintype "passive"))
      (node (ref "LED50") (pin "A") (pinfunction "A_A") (pintype "passive"))
      (node (ref "LED51") (pin "A") (pinfunction "A_A") (pintype "passive"))
      (node (ref "LED52") (pin "A") (pinfunction "A_A") (pintype "passive"))
      (node (ref "LED53") (pin "A") (pinfunction "A_A") (pintype "passive"))
      (node (ref "LED54") (pin "A") (pinfunction "A_A") (pintype "passive"))
      (node (ref "LED55") (pin "A") (pinfunction "A_A") (pintype "passive"))
      (node (ref "LED56") (pin "A") (pinfunction "A_A") (pintype "passive"))
      (node (ref "LED57") (pin "A") (pinfunction "A_A") (pintype "passive"))
      (node (ref "LED58") (pin "A") (pinfunction "A_A") (pintype "passive"))
      (node (ref "LED59") (pin "A") (pinfunction "A_A") (pintype "passive"))
      (node (ref "LED60") (pin "A") (pinfunction "A_A") (pintype "passive"))
    )
    (net (code "6") (name "Net-(LED61-C)") (class "Default")
      (node (ref "LED61") (pin "K") (pinfunction "C_K") (pintype "passive"))
      (node (ref "LED62") (pin "K") (pinfunction "C_K") (pintype "passive"))
      (node (ref "LED63") (pin "K") (pinfunction "C_K") (pintype "passive"))
      (node (ref "LED64") (pin "K") (pinfunction "C_K") (pintype "passive"))
      (node (ref "LED65") (pin "K") (pinfunction "C_K") (pintype "passive"))
      (node (ref "LED66") (pin "K") (pinfunction "C_K") (pintype "passive"))
      (node (ref "LED67") (pin "K") (pinfunction "C_K") (pintype "passive"))
      (node (ref "LED68") (pin "K") (pinfunction "C_K") (pintype "passive"))
      (node (ref "LED69") (pin "K") (pinfunction "C_K") (pintype "passive"))
      (node (ref "LED70") (pin "K") (pinfunction "C_K") (pintype "passive"))
      (node (ref "LED71") (pin "K") (pinfunction "C_K") (pintype "passive"))
      (node (ref "LED72") (pin "K") (pinfunction "C_K") (pintype "passive"))
      (node (ref "LED73") (pin "K") (pinfunction "C_K") (pintype "passive"))
      (node (ref "LED74") (pin "K") (pinfunction "C_K") (pintype "passive"))
      (node (ref "LED75") (pin "K") (pinfunction "C_K") (pintype "passive"))
      (node (ref "LED76") (pin "K") (pinfunction "C_K") (pintype "passive"))
      (node (ref "LED77") (pin "K") (pinfunction "C_K") (pintype "passive"))
      (node (ref "LED78") (pin "K") (pinfunction "C_K") (pintype "passive"))
      (node (ref "LED79") (pin "K") (pinfunction "C_K") (pintype "passive"))
      (node (ref "LED80") (pin "K") (pinfunction "C_K") (pintype "passive"))
      (node (ref "R8") (pin "1") (pinfunction "1_1") (pintype "passive"))
    )
    (net (code "7") (name "Net-(LED61-PadA)") (class "Default")
      (node (ref "LED61") (pin "A") (pinfunction "A_A") (pintype "passive"))
      (node (ref "LED62") (pin "A") (pinfunction "A_A") (pintype "passive"))
      (node (ref "LED63") (pin "A") (pinfunction "A_A") (pintype "passive"))
      (node (ref "LED64") (pin "A") (pinfunction "A_A") (pintype "passive"))
      (node (ref "LED65") (pin "A") (pinfunction "A_A") (pintype "passive"))
      (node (ref "LED66") (pin "A") (pinfunction "A_A") (pintype "passive"))
      (node (ref "LED67") (pin "A") (pinfunction "A_A") (pintype "passive"))
      (node (ref "LED68") (pin "A") (pinfunction "A_A") (pintype "passive"))
      (node (ref "LED69") (pin "A") (pinfunction "A_A") (pintype "passive"))
      (node (ref "LED70") (pin "A") (pinfunction "A_A") (pintype "passive"))
      (node (ref "LED71") (pin "A") (pinfunction "A_A") (pintype "passive"))
      (node (ref "LED72") (pin "A") (pinfunction "A_A") (pintype "passive"))
      (node (ref "LED73") (pin "A") (pinfunction "A_A") (pintype "passive"))
      (node (ref "LED74") (pin "A") (pinfunction "A_A") (pintype "passive"))
      (node (ref "LED75") (pin "A") (pinfunction "A_A") (pintype "passive"))
      (node (ref "LED76") (pin "A") (pinfunction "A_A") (pintype "passive"))
      (node (ref "LED77") (pin "A") (pinfunction "A_A") (pintype "passive"))
      (node (ref "LED78") (pin "A") (pinfunction "A_A") (pintype "passive"))
      (node (ref "LED79") (pin "A") (pinfunction "A_A") (pintype "passive"))
      (node (ref "LED80") (pin "A") (pinfunction "A_A") (pintype "passive"))
    )
    (net (code "8") (name "Net-(LED100-C)") (class "Default")
      (node (ref "LED100") (pin "K") (pinfunction "C_K") (pintype "passive"))
      (node (ref "LED81") (pin "K") (pinfunction "C_K") (pintype "passive"))
      (node (ref "LED82") (pin "K") (pinfunction "C_K") (pintype "passive"))
      (node (ref "LED83") (pin "K") (pinfunction "C_K") (pintype "passive"))
      (node (ref "LED84") (pin "K") (pinfunction "C_K") (pintype "passive"))
      (node (ref "LED85") (pin "K") (pinfunction "C_K") (pintype "passive"))
      (node (ref "LED86") (pin "K") (pinfunction "C_K") (pintype "passive"))
      (node (ref "LED87") (pin "K") (pinfunction "C_K") (pintype "passive"))
      (node (ref "LED88") (pin "K") (pinfunction "C_K") (pintype "passive"))
      (node (ref "LED89") (pin "K") (pinfunction "C_K") (pintype "passive"))
      (node (ref "LED90") (pin "K") (pinfunction "C_K") (pintype "passive"))
      (node (ref "LED91") (pin "K") (pinfunction "C_K") (pintype "passive"))
      (node (ref "LED92") (pin "K") (pinfunction "C_K") (pintype "passive"))
      (node (ref "LED93") (pin "K") (pinfunction "C_K") (pintype "passive"))
      (node (ref "LED94") (pin "K") (pinfunction "C_K") (pintype "passive"))
      (node (ref "LED95") (pin "K") (pinfunction "C_K") (pintype "passive"))
      (node (ref "LED96") (pin "K") (pinfunction "C_K") (pintype "passive"))
      (node (ref "LED97") (pin "K") (pinfunction "C_K") (pintype "passive"))
      (node (ref "LED98") (pin "K") (pinfunction "C_K") (pintype "passive"))
      (node (ref "LED99") (pin "K") (pinfunction "C_K") (pintype "passive"))
      (node (ref "R10") (pin "1") (pinfunction "1_1") (pintype "passive"))
    )
    (net (code "9") (name "Net-(LED100-PadA)") (class "Default")
      (node (ref "LED100") (pin "A") (pinfunction "A_A") (pintype "passive"))
      (node (ref "LED81") (pin "A") (pinfunction "A_A") (pintype "passive"))
      (node (ref "LED82") (pin "A") (pinfunction "A_A") (pintype "passive"))
      (node (ref "LED83") (pin "A") (pinfunction "A_A") (pintype "passive"))
      (node (ref "LED84") (pin "A") (pinfunction "A_A") (pintype "passive"))
      (node (ref "LED85") (pin "A") (pinfunction "A_A") (pintype "passive"))
      (node (ref "LED86") (pin "A") (pinfunction "A_A") (pintype "passive"))
      (node (ref "LED87") (pin "A") (pinfunction "A_A") (pintype "passive"))
      (node (ref "LED88") (pin "A") (pinfunction "A_A") (pintype "passive"))
      (node (ref "LED89") (pin "A") (pinfunction "A_A") (pintype "passive"))
      (node (ref "LED90") (pin "A") (pinfunction "A_A") (pintype "passive"))
      (node (ref "LED91") (pin "A") (pinfunction "A_A") (pintype "passive"))
      (node (ref "LED92") (pin "A") (pinfunction "A_A") (pintype "passive"))
      (node (ref "LED93") (pin "A") (pinfunction "A_A") (pintype "passive"))
      (node (ref "LED94") (pin "A") (pinfunction "A_A") (pintype "passive"))
      (node (ref "LED95") (pin "A") (pinfunction "A_A") (pintype "passive"))
      (node (ref "LED96") (pin "A") (pinfunction "A_A") (pintype "passive"))
      (node (ref "LED97") (pin "A") (pinfunction "A_A") (pintype "passive"))
      (node (ref "LED98") (pin "A") (pinfunction "A_A") (pintype "passive"))
      (node (ref "LED99") (pin "A") (pinfunction "A_A") (pintype "passive"))
    )
    (net (code "10") (name "Net-(LED101-C)") (class "Default")
      (node (ref "LED101") (pin "K") (pinfunction "C_K") (pintype "passive"))
      (node (ref "LED102") (pin "K") (pinfunction "C_K") (pintype "passive"))
      (node (ref "LED103") (pin "K") (pinfunction "C_K") (pintype "passive"))
      (node (ref "LED104") (pin "K") (pinfunction "C_K") (pintype "passive"))
      (node (ref "LED105") (pin "K") (pinfunction "C_K") (pintype "passive"))
      (node (ref "LED106") (pin "K") (pinfunction "C_K") (pintype "passive"))
      (node (ref "LED107") (pin "K") (pinfunction "C_K") (pintype "passive"))
      (node (ref "LED108") (pin "K") (pinfunction "C_K") (pintype "passive"))
      (node (ref "LED109") (pin "K") (pinfunction "C_K") (pintype "passive"))
      (node (ref "LED110") (pin "K") (pinfunction "C_K") (pintype "passive"))
      (node (ref "LED111") (pin "K") (pinfunction "C_K") (pintype "passive"))
      (node (ref "LED112") (pin "K") (pinfunction "C_K") (pintype "passive"))
      (node (ref "LED113") (pin "K") (pinfunction "C_K") (pintype "passive"))
      (node (ref "LED114") (pin "K") (pinfunction "C_K") (pintype "passive"))
      (node (ref "LED115") (pin "K") (pinfunction "C_K") (pintype "passive"))
      (node (ref "LED116") (pin "K") (pinfunction "C_K") (pintype "passive"))
      (node (ref "LED117") (pin "K") (pinfunction "C_K") (pintype "passive"))
      (node (ref "LED118") (pin "K") (pinfunction "C_K") (pintype "passive"))
      (node (ref "LED119") (pin "K") (pinfunction "C_K") (pintype "passive"))
      (node (ref "LED120") (pin "K") (pinfunction "C_K") (pintype "passive"))
      (node (ref "R12") (pin "1") (pinfunction "1_1") (pintype "passive"))
    )
    (net (code "11") (name "Net-(LED101-PadA)") (class "Default")
      (node (ref "LED101") (pin "A") (pinfunction "A_A") (pintype "passive"))
      (node (ref "LED102") (pin "A") (pinfunction "A_A") (pintype "passive"))
      (node (ref "LED103") (pin "A") (pinfunction "A_A") (pintype "passive"))
      (node (ref "LED104") (pin "A") (pinfunction "A_A") (pintype "passive"))
      (node (ref "LED105") (pin "A") (pinfunction "A_A") (pintype "passive"))
      (node (ref "LED106") (pin "A") (pinfunction "A_A") (pintype "passive"))
      (node (ref "LED107") (pin "A") (pinfunction "A_A") (pintype "passive"))
      (node (ref "LED108") (pin "A") (pinfunction "A_A") (pintype "passive"))
      (node (ref "LED109") (pin "A") (pinfunction "A_A") (pintype "passive"))
      (node (ref "LED110") (pin "A") (pinfunction "A_A") (pintype "passive"))
      (node (ref "LED111") (pin "A") (pinfunction "A_A") (pintype "passive"))
      (node (ref "LED112") (pin "A") (pinfunction "A_A") (pintype "passive"))
      (node (ref "LED113") (pin "A") (pinfunction "A_A") (pintype "passive"))
      (node (ref "LED114") (pin "A") (pinfunction "A_A") (pintype "passive"))
      (node (ref "LED115") (pin "A") (pinfunction "A_A") (pintype "passive"))
      (node (ref "LED116") (pin "A") (pinfunction "A_A") (pintype "passive"))
      (node (ref "LED117") (pin "A") (pinfunction "A_A") (pintype "passive"))
      (node (ref "LED118") (pin "A") (pinfunction "A_A") (pintype "passive"))
      (node (ref "LED119") (pin "A") (pinfunction "A_A") (pintype "passive"))
      (node (ref "LED120") (pin "A") (pinfunction "A_A") (pintype "passive"))
    )
    (net (code "12") (name "Net-(LED121-C)") (class "Default")
      (node (ref "LED121") (pin "K") (pinfunction "C_K") (pintype "passive"))
      (node (ref "LED122") (pin "K") (pinfunction "C_K") (pintype "passive"))
      (node (ref "LED123") (pin "K") (pinfunction "C_K") (pintype "passive"))
      (node (ref "LED124") (pin "K") (pinfunction "C_K") (pintype "passive"))
      (node (ref "LED125") (pin "K") (pinfunction "C_K") (pintype "passive"))
      (node (ref "LED126") (pin "K") (pinfunction "C_K") (pintype "passive"))
      (node (ref "LED127") (pin "K") (pinfunction "C_K") (pintype "passive"))
      (node (ref "LED128") (pin "K") (pinfunction "C_K") (pintype "passive"))
      (node (ref "LED129") (pin "K") (pinfunction "C_K") (pintype "passive"))
      (node (ref "LED130") (pin "K") (pinfunction "C_K") (pintype "passive"))
      (node (ref "LED131") (pin "K") (pinfunction "C_K") (pintype "passive"))
      (node (ref "LED132") (pin "K") (pinfunction "C_K") (pintype "passive"))
      (node (ref "LED133") (pin "K") (pinfunction "C_K") (pintype "passive"))
      (node (ref "LED134") (pin "K") (pinfunction "C_K") (pintype "passive"))
      (node (ref "LED135") (pin "K") (pinfunction "C_K") (pintype "passive"))
      (node (ref "LED136") (pin "K") (pinfunction "C_K") (pintype "passive"))
      (node (ref "LED137") (pin "K") (pinfunction "C_K") (pintype "passive"))
      (node (ref "LED138") (pin "K") (pinfunction "C_K") (pintype "passive"))
      (node (ref "LED139") (pin "K") (pinfunction "C_K") (pintype "passive"))
      (node (ref "LED140") (pin "K") (pinfunction "C_K") (pintype "passive"))
      (node (ref "R14") (pin "1") (pinfunction "1_1") (pintype "passive"))
    )
    (net (code "13") (name "Net-(LED121-PadA)") (class "Default")
      (node (ref "LED121") (pin "A") (pinfunction "A_A") (pintype "passive"))
      (node (ref "LED122") (pin "A") (pinfunction "A_A") (pintype "passive"))
      (node (ref "LED123") (pin "A") (pinfunction "A_A") (pintype "passive"))
      (node (ref "LED124") (pin "A") (pinfunction "A_A") (pintype "passive"))
      (node (ref "LED125") (pin "A") (pinfunction "A_A") (pintype "passive"))
      (node (ref "LED126") (pin "A") (pinfunction "A_A") (pintype "passive"))
      (node (ref "LED127") (pin "A") (pinfunction "A_A") (pintype "passive"))
      (node (ref "LED128") (pin "A") (pinfunction "A_A") (pintype "passive"))
      (node (ref "LED129") (pin "A") (pinfunction "A_A") (pintype "passive"))
      (node (ref "LED130") (pin "A") (pinfunction "A_A") (pintype "passive"))
      (node (ref "LED131") (pin "A") (pinfunction "A_A") (pintype "passive"))
      (node (ref "LED132") (pin "A") (pinfunction "A_A") (pintype "passive"))
      (node (ref "LED133") (pin "A") (pinfunction "A_A") (pintype "passive"))
      (node (ref "LED134") (pin "A") (pinfunction "A_A") (pintype "passive"))
      (node (ref "LED135") (pin "A") (pinfunction "A_A") (pintype "passive"))
      (node (ref "LED136") (pin "A") (pinfunction "A_A") (pintype "passive"))
      (node (ref "LED137") (pin "A") (pinfunction "A_A") (pintype "passive"))
      (node (ref "LED138") (pin "A") (pinfunction "A_A") (pintype "passive"))
      (node (ref "LED139") (pin "A") (pinfunction "A_A") (pintype "passive"))
      (node (ref "LED140") (pin "A") (pinfunction "A_A") (pintype "passive"))
    )
    (net (code "14") (name "Net-(R1-Pad2)") (class "Default")
      (node (ref "R1") (pin "2") (pinfunction "2_2") (pintype "passive"))
      (node (ref "T1") (pin "C") (pinfunction "C_C") (pintype "passive"))
    )
    (net (code "15") (name "Net-(R2-Pad1)") (class "Default")
      (node (ref "R2") (pin "1") (pinfunction "1_1") (pintype "passive"))
      (node (ref "T1") (pin "B") (pinfunction "B_B") (pintype "passive"))
    )
    (net (code "16") (name "Net-(R3-Pad1)") (class "Default")
      (node (ref "R3") (pin "1") (pinfunction "1_1") (pintype "passive"))
      (node (ref "T2") (pin "B") (pinfunction "B_B") (pintype "passive"))
    )
    (net (code "17") (name "Net-(R4-Pad2)") (class "Default")
      (node (ref "R4") (pin "2") (pinfunction "2_2") (pintype "passive"))
      (node (ref "T2") (pin "C") (pinfunction "C_C") (pintype "passive"))
    )
    (net (code "18") (name "Net-(R5-Pad1)") (class "Default")
      (node (ref "R5") (pin "1") (pinfunction "1_1") (pintype "passive"))
      (node (ref "T3") (pin "B") (pinfunction "B_B") (pintype "passive"))
    )
    (net (code "19") (name "Net-(R6-Pad2)") (class "Default")
      (node (ref "R6") (pin "2") (pinfunction "2_2") (pintype "passive"))
      (node (ref "T3") (pin "C") (pinfunction "C_C") (pintype "passive"))
    )
    (net (code "20") (name "Net-(R7-Pad1)") (class "Default")
      (node (ref "R7") (pin "1") (pinfunction "1_1") (pintype "passive"))
      (node (ref "T4") (pin "B") (pinfunction "B_B") (pintype "passive"))
    )
    (net (code "21") (name "Net-(R8-Pad2)") (class "Default")
      (node (ref "R8") (pin "2") (pinfunction "2_2") (pintype "passive"))
      (node (ref "T4") (pin "C") (pinfunction "C_C") (pintype "passive"))
    )
    (net (code "22") (name "Net-(R9-Pad1)") (class "Default")
      (node (ref "R9") (pin "1") (pinfunction "1_1") (pintype "passive"))
      (node (ref "T5") (pin "B") (pinfunction "B_B") (pintype "passive"))
    )
    (net (code "23") (name "Net-(R10-Pad2)") (class "Default")
      (node (ref "R10") (pin "2") (pinfunction "2_2") (pintype "passive"))
      (node (ref "T5") (pin "C") (pinfunction "C_C") (pintype "passive"))
    )
    (net (code "24") (name "Net-(R11-Pad1)") (class "Default")
      (node (ref "R11") (pin "1") (pinfunction "1_1") (pintype "passive"))
      (node (ref "T6") (pin "B") (pinfunction "B_B") (pintype "passive"))
    )
    (net (code "25") (name "Net-(R12-Pad2)") (class "Default")
      (node (ref "R12") (pin "2") (pinfunction "2_2") (pintype "passive"))
      (node (ref "T6") (pin "C") (pinfunction "C_C") (pintype "passive"))
    )
    (net (code "26") (name "Net-(R13-Pad1)") (class "Default")
      (node (ref "R13") (pin "1") (pinfunction "1_1") (pintype "passive"))
      (node (ref "T7") (pin "B") (pinfunction "B_B") (pintype "passive"))
    )
    (net (code "27") (name "Net-(R14-Pad2)") (class "Default")
      (node (ref "R14") (pin "2") (pinfunction "2_2") (pintype "passive"))
      (node (ref "T7") (pin "C") (pinfunction "C_C") (pintype "passive"))
    )
    (net (code "28") (name "SUP") (class "Default")
      (node (ref "T1") (pin "E") (pinfunction "E_E") (pintype "passive"))
    )
    (net (code "29") (name "VCC") (class "Default")
      (node (ref "LED1") (pin "A") (pinfunction "A_A") (pintype "passive"))
      (node (ref "LED10") (pin "A") (pinfunction "A_A") (pintype "passive"))
      (node (ref "LED11") (pin "A") (pinfunction "A_A") (pintype "passive"))
      (node (ref "LED12") (pin "A") (pinfunction "A_A") (pintype "passive"))
      (node (ref "LED13") (pin "A") (pinfunction "A_A") (pintype "passive"))
      (node (ref "LED14") (pin "A") (pinfunction "A_A") (pintype "passive"))
      (node (ref "LED15") (pin "A") (pinfunction "A_A") (pintype "passive"))
      (node (ref "LED16") (pin "A") (pinfunction "A_A") (pintype "passive"))
      (node (ref "LED17") (pin "A") (pinfunction "A_A") (pintype "passive"))
      (node (ref "LED18") (pin "A") (pinfunction "A_A") (pintype "passive"))
      (node (ref "LED19") (pin "A") (pinfunction "A_A") (pintype "passive"))
      (node (ref "LED2") (pin "A") (pinfunction "A_A") (pintype "passive"))
      (node (ref "LED20") (pin "A") (pinfunction "A_A") (pintype "passive"))
      (node (ref "LED3") (pin "A") (pinfunction "A_A") (pintype "passive"))
      (node (ref "LED4") (pin "A") (pinfunction "A_A") (pintype "passive"))
      (node (ref "LED5") (pin "A") (pinfunction "A_A") (pintype "passive"))
      (node (ref "LED6") (pin "A") (pinfunction "A_A") (pintype "passive"))
      (node (ref "LED7") (pin "A") (pinfunction "A_A") (pintype "passive"))
      (node (ref "LED8") (pin "A") (pinfunction "A_A") (pintype "passive"))
      (node (ref "LED9") (pin "A") (pinfunction "A_A") (pintype "passive"))
    )
    (net (code "30") (name "unconnected-(MGT2-PadP$1)") (class "Default")
      (node (ref "MGT2") (pin "P$1") (pinfunction "P$1_P$1") (pintype "bidirectional"))
    )
    (net (code "31") (name "unconnected-(MGT3-PadP$1)") (class "Default")
      (node (ref "MGT3") (pin "P$1") (pinfunction "P$1_P$1") (pintype "bidirectional"))
    )
    (net (code "32") (name "unconnected-(MGT4-PadP$1)") (class "Default")
      (node (ref "MGT4") (pin "P$1") (pinfunction "P$1_P$1") (pintype "bidirectional"))
    )
    (net (code "33") (name "unconnected-(MGT6-PadP$1)") (class "Default")
      (node (ref "MGT6") (pin "P$1") (pinfunction "P$1_P$1") (pintype "bidirectional"))
    )
    (net (code "34") (name "unconnected-(MGT8-PadP$1)") (class "Default")
      (node (ref "MGT8") (pin "P$1") (pinfunction "P$1_P$1") (pintype "bidirectional"))
    )
    (net (code "35") (name "unconnected-(MGT9-PadP$1)") (class "Default")
      (node (ref "MGT9") (pin "P$1") (pinfunction "P$1_P$1") (pintype "bidirectional"))
    )
    (net (code "36") (name "unconnected-(R2-Pad2)") (class "Default")
      (node (ref "R2") (pin "2") (pinfunction "2_2") (pintype "passive"))
    )
    (net (code "37") (name "unconnected-(R3-Pad2)") (class "Default")
      (node (ref "R3") (pin "2") (pinfunction "2_2") (pintype "passive"))
    )
    (net (code "38") (name "unconnected-(R5-Pad2)") (class "Default")
      (node (ref "R5") (pin "2") (pinfunction "2_2") (pintype "passive"))
    )
    (net (code "39") (name "unconnected-(R7-Pad2)") (class "Default")
      (node (ref "R7") (pin "2") (pinfunction "2_2") (pintype "passive"))
    )
    (net (code "40") (name "unconnected-(R9-Pad2)") (class "Default")
      (node (ref "R9") (pin "2") (pinfunction "2_2") (pintype "passive"))
    )
    (net (code "41") (name "unconnected-(R11-Pad2)") (class "Default")
      (node (ref "R11") (pin "2") (pinfunction "2_2") (pintype "passive"))
    )
    (net (code "42") (name "unconnected-(R13-Pad2)") (class "Default")
      (node (ref "R13") (pin "2") (pinfunction "2_2") (pintype "passive"))
    )
    (net (code "43") (name "unconnected-(T2-PadE)") (class "Default")
      (node (ref "T2") (pin "E") (pinfunction "E_E") (pintype "passive"))
    )
    (net (code "44") (name "unconnected-(T3-PadE)") (class "Default")
      (node (ref "T3") (pin "E") (pinfunction "E_E") (pintype "passive"))
    )
    (net (code "45") (name "unconnected-(T4-PadE)") (class "Default")
      (node (ref "T4") (pin "E") (pinfunction "E_E") (pintype "passive"))
    )
    (net (code "46") (name "unconnected-(T5-PadE)") (class "Default")
      (node (ref "T5") (pin "E") (pinfunction "E_E") (pintype "passive"))
    )
    (net (code "47") (name "unconnected-(T6-PadE)") (class "Default")
      (node (ref "T6") (pin "E") (pinfunction "E_E") (pintype "passive"))
    )
    (net (code "48") (name "unconnected-(T7-PadE)") (class "Default")
      (node (ref "T7") (pin "E") (pinfunction "E_E") (pintype "passive"))
    )
    (net (code "49") (name "unconnected-(X1-P1-PadL1)") (class "Default")
      (node (ref "X1") (pin "L1") (pinfunction "P1_L1") (pintype "bidirectional"))
    )
    (net (code "50") (name "unconnected-(X1-P2-PadL2)") (class "Default")
      (node (ref "X1") (pin "L2") (pinfunction "P2_L2") (pintype "bidirectional"))
    )
  )
)
